# STM32F4xx_Schematic.net
KiCad netlist of a schematic drawn in Altium Designer
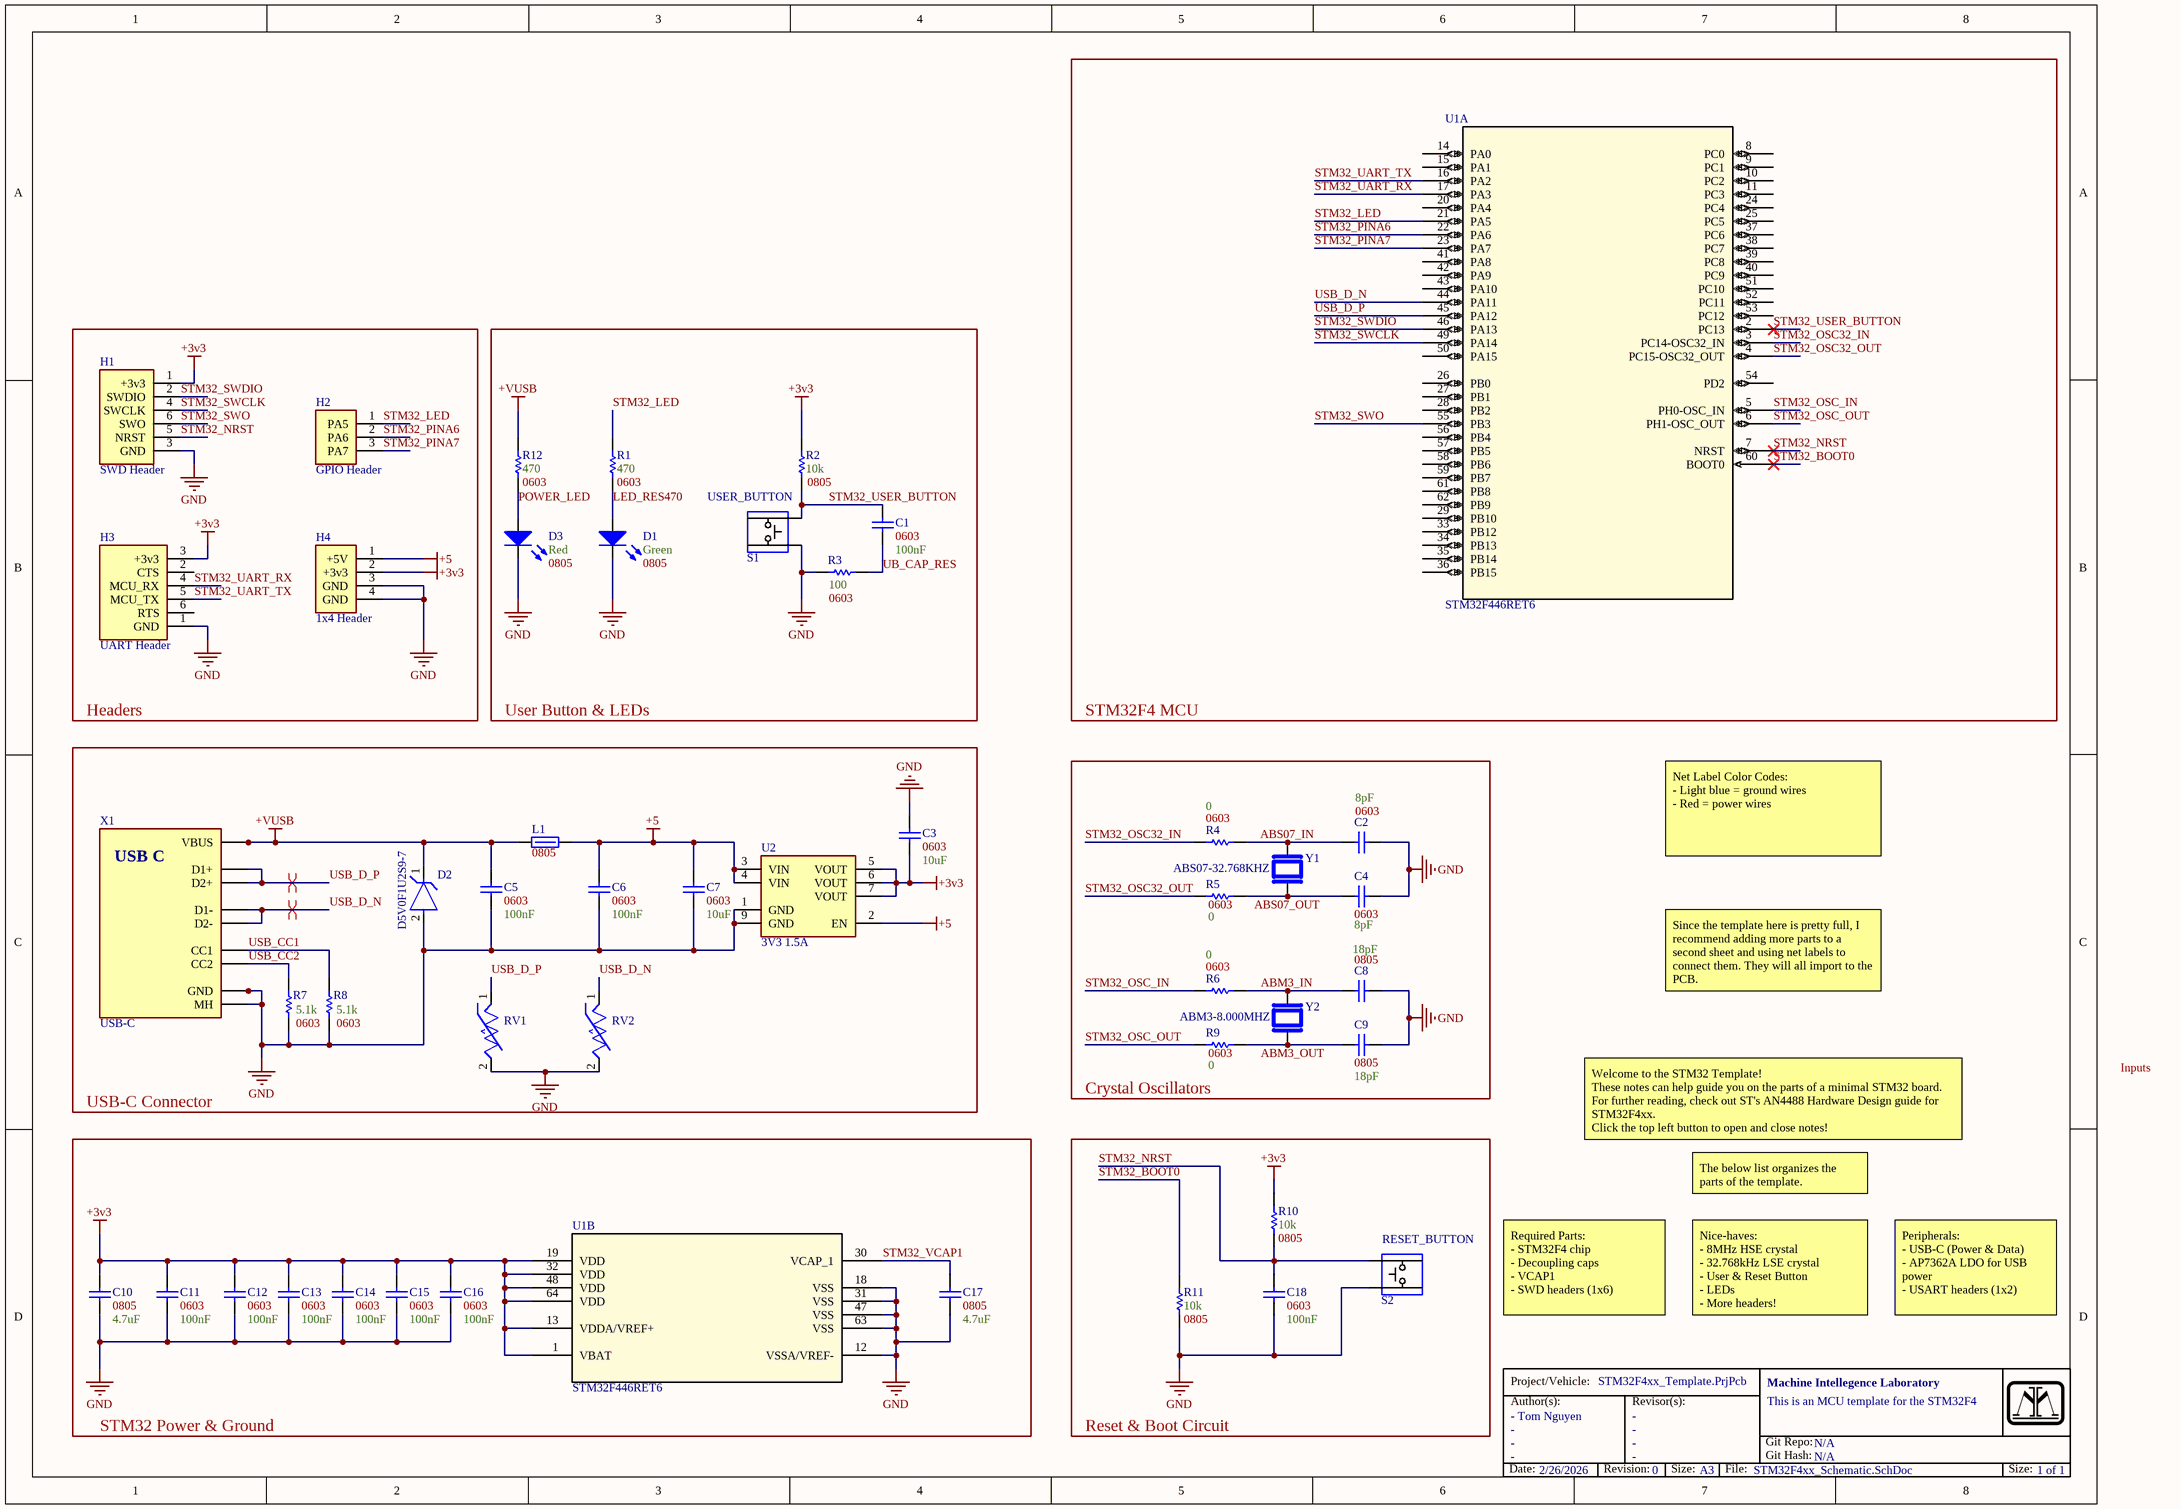
[diagram p0: STM32F4xx_Schematic.SchDoc]

(export (version "E")
  (design (tool "Eeschema 10.0.6"))
  (components
    (comp (ref "C1")
      (value "[Cap] 0603 0.1uF 10% 16V")
      (footprint "[Cap] SMD 0603")
      (description "CC0603KRX7R7BB104")
      (fields
        (field (name "SIZE PACKAGE") "0603")
        (field (name "TOLERANCE") "10%")
        (field (name "CAPACITANCE") "100nF")
      )
      (libsource (lib "Capacitors") (part "[Cap] 0603 0.1uF 10% 16V"))
    )
    (comp (ref "C2")
      (value "8pF")
      (footprint "[Cap] 0603 8pF ±0.1pF 50V")
      (description "GRM1555C1H8R0BA01D")
      (fields
        (field (name "SIZ") "0603")
        (field (name "CAPACITANCE") "8pF")
        (field (name "COPYRIGHT") "Copyright (C) 2026 Ultra Librarian. All rights reserved.")
      )
      (libsource (lib "STM32F4xx") (part "[Cap] 0603 8pF ±0.1pF 50V"))
    )
    (comp (ref "C3")
      (value "[Cap] 0603 10uF 10% 10V")
      (footprint "[Cap] SMD 0603")
      (description "CL10A106KP8NNNC")
      (fields
        (field (name "SIZE PACKAGE") "0603")
        (field (name "TOLERANCE") "10%")
        (field (name "CAPACITANCE") "10uF")
      )
      (libsource (lib "Capacitors") (part "[Cap] 0603 10uF 10% 10V"))
    )
    (comp (ref "C4")
      (value "8pF")
      (footprint "[Cap] 0603 8pF ±0.1pF 50V")
      (description "GRM1555C1H8R0BA01D")
      (fields
        (field (name "SIZ") "0603")
        (field (name "CAPACITANCE") "8pF")
        (field (name "COPYRIGHT") "Copyright (C) 2026 Ultra Librarian. All rights reserved.")
      )
      (libsource (lib "STM32F4xx") (part "[Cap] 0603 8pF ±0.1pF 50V"))
    )
    (comp (ref "C5")
      (value "[Cap] 0603 0.1uF 10% 16V")
      (footprint "[Cap] SMD 0603")
      (description "CC0603KRX7R7BB104")
      (fields
        (field (name "SIZE PACKAGE") "0603")
        (field (name "TOLERANCE") "10%")
        (field (name "CAPACITANCE") "100nF")
      )
      (libsource (lib "Capacitors") (part "[Cap] 0603 0.1uF 10% 16V"))
    )
    (comp (ref "C6")
      (value "[Cap] 0603 0.1uF 10% 16V")
      (footprint "[Cap] SMD 0603")
      (description "CC0603KRX7R7BB104")
      (fields
        (field (name "SIZE PACKAGE") "0603")
        (field (name "TOLERANCE") "10%")
        (field (name "CAPACITANCE") "100nF")
      )
      (libsource (lib "Capacitors") (part "[Cap] 0603 0.1uF 10% 16V"))
    )
    (comp (ref "C7")
      (value "[Cap] 0603 10uF 10% 10V")
      (footprint "[Cap] SMD 0603")
      (description "CL10A106KP8NNNC")
      (fields
        (field (name "SIZE PACKAGE") "0603")
        (field (name "TOLERANCE") "10%")
        (field (name "CAPACITANCE") "10uF")
      )
      (libsource (lib "Capacitors") (part "[Cap] 0603 10uF 10% 10V"))
    )
    (comp (ref "C8")
      (value "[Cap] 0805 18pF ±5% 250V")
      (footprint "[Cap] 0805 ±5% 250V")
      (description "GQM2195C2E180JB12D")
      (fields
        (field (name "MF") "Murata")
        (field (name "MP") "GQM2195C2E270JB12D")
        (field (name "SIZE") "0805")
        (field (name "CAPACITANCE") "18pF")
      )
      (libsource (lib "STM32F4xx") (part "[Cap] 0805 18pF ±5% 250V"))
    )
    (comp (ref "C9")
      (value "[Cap] 0805 18pF ±5% 250V")
      (footprint "[Cap] 0805 ±5% 250V")
      (description "GQM2195C2E180JB12D")
      (fields
        (field (name "MF") "Murata")
        (field (name "MP") "GQM2195C2E270JB12D")
        (field (name "SIZE") "0805")
        (field (name "CAPACITANCE") "18pF")
      )
      (libsource (lib "STM32F4xx") (part "[Cap] 0805 18pF ±5% 250V"))
    )
    (comp (ref "C10")
      (value "[Cap] 0805 4.7uF 10% 50V")
      (footprint "[Cap] SMD 0805")
      (description "GRT21BR61H475KE13L")
      (fields
        (field (name "SIZE PACKAGE") "0805")
        (field (name "TOLERANCE") "10%")
        (field (name "CAPACITANCE") "4.7uF")
      )
      (libsource (lib "Capacitors") (part "[Cap] 0805 4.7uF 10% 50V"))
    )
    (comp (ref "C11")
      (value "[Cap] 0603 0.1uF 10% 16V")
      (footprint "[Cap] SMD 0603")
      (description "CC0603KRX7R7BB104")
      (fields
        (field (name "SIZE PACKAGE") "0603")
        (field (name "TOLERANCE") "10%")
        (field (name "CAPACITANCE") "100nF")
      )
      (libsource (lib "Capacitors") (part "[Cap] 0603 0.1uF 10% 16V"))
    )
    (comp (ref "C12")
      (value "[Cap] 0603 0.1uF 10% 16V")
      (footprint "[Cap] SMD 0603")
      (description "CC0603KRX7R7BB104")
      (fields
        (field (name "SIZE PACKAGE") "0603")
        (field (name "TOLERANCE") "10%")
        (field (name "CAPACITANCE") "100nF")
      )
      (libsource (lib "Capacitors") (part "[Cap] 0603 0.1uF 10% 16V"))
    )
    (comp (ref "C13")
      (value "[Cap] 0603 0.1uF 10% 16V")
      (footprint "[Cap] SMD 0603")
      (description "CC0603KRX7R7BB104")
      (fields
        (field (name "SIZE PACKAGE") "0603")
        (field (name "TOLERANCE") "10%")
        (field (name "CAPACITANCE") "100nF")
      )
      (libsource (lib "Capacitors") (part "[Cap] 0603 0.1uF 10% 16V"))
    )
    (comp (ref "C14")
      (value "[Cap] 0603 0.1uF 10% 16V")
      (footprint "[Cap] SMD 0603")
      (description "CC0603KRX7R7BB104")
      (fields
        (field (name "SIZE PACKAGE") "0603")
        (field (name "TOLERANCE") "10%")
        (field (name "CAPACITANCE") "100nF")
      )
      (libsource (lib "Capacitors") (part "[Cap] 0603 0.1uF 10% 16V"))
    )
    (comp (ref "C15")
      (value "[Cap] 0603 0.1uF 10% 16V")
      (footprint "[Cap] SMD 0603")
      (description "CC0603KRX7R7BB104")
      (fields
        (field (name "SIZE PACKAGE") "0603")
        (field (name "TOLERANCE") "10%")
        (field (name "CAPACITANCE") "100nF")
      )
      (libsource (lib "Capacitors") (part "[Cap] 0603 0.1uF 10% 16V"))
    )
    (comp (ref "C16")
      (value "[Cap] 0603 0.1uF 10% 16V")
      (footprint "[Cap] SMD 0603")
      (description "CC0603KRX7R7BB104")
      (fields
        (field (name "SIZE PACKAGE") "0603")
        (field (name "TOLERANCE") "10%")
        (field (name "CAPACITANCE") "100nF")
      )
      (libsource (lib "Capacitors") (part "[Cap] 0603 0.1uF 10% 16V"))
    )
    (comp (ref "C17")
      (value "[Cap] 0805 4.7uF 10% 50V")
      (footprint "[Cap] SMD 0805")
      (description "GRT21BR61H475KE13L")
      (fields
        (field (name "SIZE PACKAGE") "0805")
        (field (name "TOLERANCE") "10%")
        (field (name "CAPACITANCE") "4.7uF")
      )
      (libsource (lib "Capacitors") (part "[Cap] 0805 4.7uF 10% 50V"))
    )
    (comp (ref "C18")
      (value "[Cap] 0603 0.1uF 10% 16V")
      (footprint "[Cap] SMD 0603")
      (description "CC0603KRX7R7BB104")
      (fields
        (field (name "SIZE PACKAGE") "0603")
        (field (name "TOLERANCE") "10%")
        (field (name "CAPACITANCE") "100nF")
      )
      (libsource (lib "Capacitors") (part "[Cap] 0603 0.1uF 10% 16V"))
    )
    (comp (ref "D1")
      (value "[LED] SMD 0805 Green")
      (footprint "[LED] SMD 0805")
      (description "LG R971-KN-1-0-20-R18")
      (fields (field (name "COLOR") "Green") (field (name "SIZE PACKAGE") "0805"))
      (libsource (lib "LEDs") (part "[LED] SMD 0805 Green"))
    )
    (comp (ref "D2")
      (value "Cathode side marked by line")
      (footprint "[TVS] Unidirectional for 5V ESD")
      (description "D5V0F1U2S9-7")
      (fields
        (field (name "SUPPLIER PART NUMBER 1") "D5V0F1U2S9-7")
        (field (name "COPYRIGHT") "Copyright (C) 2025 Ultra Librarian. All rights reserved.")
      )
      (libsource (lib "STM32F4xx") (part "[TVS] Unidirectional for 5V ESD"))
    )
    (comp (ref "D3")
      (value "[LED] SMD 0805 Red")
      (footprint "[LED] SMD 0805")
      (description "LS R976-NR-1-0-20-R18")
      (fields (field (name "COLOR") "Red") (field (name "SIZE PACKAGE") "0805"))
      (libsource (lib "LEDs") (part "[LED] SMD 0805 Red"))
    )
    (comp (ref "H1")
      (value "SWD Header")
      (footprint "[Header] 1x6 Male STM32 SWD")
      (description "2.54mm pitch")
      (libsource (lib "STM32F4xx") (part "[Header] 1x6 Male STM32 SWD"))
    )
    (comp (ref "H2")
      (value "GPIO Header")
      (footprint "[Header] 1x3 Male GPIO")
      (description "2.54mm pitch")
      (libsource (lib "STM32F4xx") (part "[Header] 1x3 Male GPIO"))
    )
    (comp (ref "H3")
      (value "UART Header")
      (footprint "[Header] 1x6 Male STM32 UART")
      (description "2.54mm pitch")
      (libsource (lib "STM32F4xx") (part "[Header] 1x6 Male STM32 UART"))
    )
    (comp (ref "H4")
      (value "1x4 Header")
      (footprint "[Header] 1x4 Male Power")
      (description "2.54mm pitch")
      (libsource (lib "STM32F4xx") (part "[Header] 1x4 Male Power"))
    )
    (comp (ref "L1")
      (value "652-MH2029-300Y")
      (footprint "[Ferrite] SMD 0805")
      (fields (field (name "SIZE PACKAGE") "0805"))
      (libsource (lib "Ferrite Beads") (part "[Ferrite] SMD 0805 3A 30ohm"))
    )
    (comp (ref "R1")
      (value "RC0603JR-13470RL")
      (footprint "RESC1608X55X25LL10T15")
      (fields
        (field (name "MANUFACTURER") "Yageo")
        (field (name "RESISTANCE") "470")
        (field (name "SIZE PACKAGE") "0603")
      )
      (libsource (lib "Altium Content Vault") (part "RES"))
    )
    (comp (ref "R2")
      (value "[10k] SMD 0603 1% 1/8W")
      (footprint "[Res] SMD 0603")
      (description "RC0805JR-0710KL")
      (fields
        (field (name "TOLERANCE") "5%")
        (field (name "RESISTANCE") "10k")
        (field (name "SIZE PACKAGE") "0805")
      )
      (libsource (lib "Resistors") (part "[10k] SMD 0603 1% 1/8W"))
    )
    (comp (ref "R3")
      (value "[100] SMD 0603 1% 1/10W")
      (footprint "[Res] SMD 0603")
      (description "RC0603FR-07100RL")
      (fields
        (field (name "TOLERANCE") "1%")
        (field (name "RESISTANCE") "100")
        (field (name "SIZE PACKAGE") "0603")
      )
      (libsource (lib "Resistors") (part "[100] SMD 0603 1% 1/10W"))
    )
    (comp (ref "R4")
      (value "[0] SMD 0603 5% 1/10W")
      (footprint "[0] SMD 0603 5% 1/10W")
      (description "RC0603JR-070RL")
      (fields
        (field (name "MF") "Yageo")
        (field (name "RESISTANCE") "0")
        (field (name "SIZE PACKAGE") "0603")
        (field (name "TOLERANCE") "5%")
      )
      (libsource (lib "STM32F4xx") (part "[0] SMD 0603 5% 1/10W"))
    )
    (comp (ref "R5")
      (value "[0] SMD 0603 5% 1/10W")
      (footprint "[0] SMD 0603 5% 1/10W")
      (description "RC0603JR-070RL")
      (fields
        (field (name "MF") "Yageo")
        (field (name "RESISTANCE") "0")
        (field (name "SIZE PACKAGE") "0603")
        (field (name "TOLERANCE") "5%")
      )
      (libsource (lib "STM32F4xx") (part "[0] SMD 0603 5% 1/10W"))
    )
    (comp (ref "R6")
      (value "[0] SMD 0603 5% 1/10W")
      (footprint "[0] SMD 0603 5% 1/10W")
      (description "RC0603JR-070RL")
      (fields
        (field (name "MF") "Yageo")
        (field (name "RESISTANCE") "0")
        (field (name "SIZE PACKAGE") "0603")
        (field (name "TOLERANCE") "5%")
      )
      (libsource (lib "STM32F4xx") (part "[0] SMD 0603 5% 1/10W"))
    )
    (comp (ref "R7")
      (value "[5.1k] SMD 0603 1% 1/10W")
      (footprint "[Res] SMD 0603")
      (description "RC0603FR-075K1L")
      (fields
        (field (name "TOLERANCE") "1%")
        (field (name "RESISTANCE") "5.1k")
        (field (name "SIZE PACKAGE") "0603")
      )
      (libsource (lib "Resistors") (part "[5.1k] SMD 0603 1% 1/10W"))
    )
    (comp (ref "R8")
      (value "[5.1k] SMD 0603 1% 1/10W")
      (footprint "[Res] SMD 0603")
      (description "RC0603FR-075K1L")
      (fields
        (field (name "TOLERANCE") "1%")
        (field (name "RESISTANCE") "5.1k")
        (field (name "SIZE PACKAGE") "0603")
      )
      (libsource (lib "Resistors") (part "[5.1k] SMD 0603 1% 1/10W"))
    )
    (comp (ref "R9")
      (value "[0] SMD 0603 5% 1/10W")
      (footprint "[0] SMD 0603 5% 1/10W")
      (description "RC0603JR-070RL")
      (fields
        (field (name "MF") "Yageo")
        (field (name "RESISTANCE") "0")
        (field (name "SIZE PACKAGE") "0603")
        (field (name "TOLERANCE") "5%")
      )
      (libsource (lib "STM32F4xx") (part "[0] SMD 0603 5% 1/10W"))
    )
    (comp (ref "R10")
      (value "[10k] SMD 0603 1% 1/8W")
      (footprint "[Res] SMD 0603")
      (description "RC0805JR-0710KL")
      (fields
        (field (name "TOLERANCE") "5%")
        (field (name "RESISTANCE") "10k")
        (field (name "SIZE PACKAGE") "0805")
      )
      (libsource (lib "Resistors") (part "[10k] SMD 0603 1% 1/8W"))
    )
    (comp (ref "R11")
      (value "[10k] SMD 0603 1% 1/8W")
      (footprint "[Res] SMD 0603")
      (description "RC0805JR-0710KL")
      (fields
        (field (name "TOLERANCE") "5%")
        (field (name "RESISTANCE") "10k")
        (field (name "SIZE PACKAGE") "0805")
      )
      (libsource (lib "Resistors") (part "[10k] SMD 0603 1% 1/8W"))
    )
    (comp (ref "R12")
      (value "RC0603JR-13470RL")
      (footprint "RESC1608X55X25LL10T15")
      (fields
        (field (name "MANUFACTURER") "Yageo")
        (field (name "RESISTANCE") "470")
        (field (name "SIZE PACKAGE") "0603")
      )
      (libsource (lib "Altium Content Vault") (part "RES"))
    )
    (comp (ref "RV1")
      (value "[ESD] SMD Varistor for USB 3.3V lines")
      (footprint "[ESD] SMD Varistor for USB 3.3V lines")
      (description "Varistor 1 Circuit Surface Mount, MLCV 0603 (1608 Metric) CG0603MLU-05E")
      (fields (field (name "MF") "Bourns") (field (name "MP") "CG0603MLU-05E"))
      (libsource (lib "STM32F4xx") (part "[ESD] SMD Varistor for USB 3.3V lines"))
    )
    (comp (ref "RV2")
      (value "[ESD] SMD Varistor for USB 3.3V lines")
      (footprint "[ESD] SMD Varistor for USB 3.3V lines")
      (description "Varistor 1 Circuit Surface Mount, MLCV 0603 (1608 Metric) CG0603MLU-05E")
      (fields (field (name "MF") "Bourns") (field (name "MP") "CG0603MLU-05E"))
      (libsource (lib "STM32F4xx") (part "[ESD] SMD Varistor for USB 3.3V lines"))
    )
    (comp (ref "S1")
      (value "Standard pushbutton")
      (footprint "[SPST] Pushbutton")
      (libsource (lib "Switches") (part "[SPST] Pushbutton"))
    )
    (comp (ref "S2")
      (value "Standard pushbutton")
      (footprint "[SPST] Pushbutton")
      (libsource (lib "") (part "[SPST] Pushbutton_1"))
    )
    (comp (ref "U1")
      (value "STM32F446RET6")
      (footprint "STM32F446RET6")
      (fields (field (name "COPYRIGHT") "Copyright (C) 2025 Ultra Librarian. All rights reserved."))
      (libsource (lib "STM32F4xx") (part "STM32F446RET6"))
    )
    (comp (ref "U2")
      (value "3V3 1.5A")
      (footprint "[Linear] 3V3 1.5A")
      (description "AP7362A-33SP-13")
      (libsource (lib "Voltage Regulators") (part "[Linear] 3V3 1.5A"))
    )
    (comp (ref "X1")
      (value "USB-C")
      (footprint "[USB] USB-C Right-Angle")
      (libsource (lib "STM32F4xx") (part "[USB] Type-C Right-Angle"))
    )
    (comp (ref "Y1")
      (value "ABS07-32.768KHZ")
      (footprint "ABS07-32.768KHZ")
      (description "ABS07-32.768KHZ-9-T, 32.768 kHz Â±20ppm Crystal 9pF 70 kOhms 2-SMD, No Lead")
      (fields (field (name "MF") "Abracon") (field (name "MP") "ABS07-32.768KHZ-9-T"))
      (libsource (lib "STM32F4xx") (part "ABS07-32.768KHZ"))
    )
    (comp (ref "Y2")
      (value "ABM3-8.000MHZ")
      (footprint "ABM3-8.000MHZ")
      (description "ABM3-8.000MHZ-D2Y-T, 8 MHz Â±20ppm Crystal 18pF 140 Ohms 2-SMD, No Lead")
      (fields (field (name "MP") "ABM3-8.000MHZ-D2Y-T") (field (name "MF") "Abracon"))
      (libsource (lib "STM32F4xx") (part "ABM3-8.000MHZ"))
    )
  )
  (nets
    (net (code "1") (name "+3v3") (class "Default")
      (node (ref "C10") (pin "2") (pinfunction "2_2") (pintype "passive"))
      (node (ref "C11") (pin "2") (pinfunction "2_2") (pintype "passive"))
      (node (ref "C12") (pin "1") (pinfunction "1_1") (pintype "passive"))
      (node (ref "C13") (pin "1") (pinfunction "1_1") (pintype "passive"))
      (node (ref "C14") (pin "1") (pinfunction "1_1") (pintype "passive"))
      (node (ref "C15") (pin "1") (pinfunction "1_1") (pintype "passive"))
      (node (ref "C16") (pin "2") (pinfunction "2_2") (pintype "passive"))
      (node (ref "C3") (pin "1") (pinfunction "1_1") (pintype "passive"))
      (node (ref "H1") (pin "1") (pinfunction "+3v3_1") (pintype "passive"))
      (node (ref "H3") (pin "3") (pinfunction "+3v3_3") (pintype "passive"))
      (node (ref "H4") (pin "2") (pinfunction "+3v3_2") (pintype "passive"))
      (node (ref "R10") (pin "2") (pinfunction "2_2") (pintype "passive"))
      (node (ref "R2") (pin "1") (pinfunction "1_1") (pintype "passive"))
      (node (ref "U1") (pin "1") (pinfunction "VBAT_1") (pintype "power_in"))
      (node (ref "U1") (pin "13") (pinfunction "VDDA/VREF+_13") (pintype "power_in"))
      (node (ref "U1") (pin "19") (pinfunction "VDD_19") (pintype "power_in"))
      (node (ref "U1") (pin "32") (pinfunction "VDD_32") (pintype "power_in"))
      (node (ref "U1") (pin "48") (pinfunction "VDD_48") (pintype "power_in"))
      (node (ref "U1") (pin "64") (pinfunction "VDD_64") (pintype "power_in"))
      (node (ref "U2") (pin "5") (pinfunction "VOUT_5") (pintype "passive"))
      (node (ref "U2") (pin "6") (pinfunction "VOUT_6") (pintype "passive"))
      (node (ref "U2") (pin "7") (pinfunction "VOUT_7") (pintype "passive"))
    )
    (net (code "2") (name "+5") (class "Default")
      (node (ref "C6") (pin "1") (pinfunction "1_1") (pintype "passive"))
      (node (ref "C7") (pin "2") (pinfunction "2_2") (pintype "passive"))
      (node (ref "H4") (pin "1") (pinfunction "+5V_1") (pintype "passive"))
      (node (ref "L1") (pin "2") (pinfunction "2_2") (pintype "passive"))
      (node (ref "U2") (pin "2") (pinfunction "EN_2") (pintype "passive"))
      (node (ref "U2") (pin "3") (pinfunction "VIN_3") (pintype "passive"))
      (node (ref "U2") (pin "4") (pinfunction "VIN_4") (pintype "passive"))
    )
    (net (code "3") (name "+VUSB") (class "Default")
      (node (ref "C5") (pin "1") (pinfunction "1_1") (pintype "passive"))
      (node (ref "D2") (pin "1") (pinfunction "1_1") (pintype "passive"))
      (node (ref "L1") (pin "1") (pinfunction "1_1") (pintype "passive"))
      (node (ref "R12") (pin "1") (pinfunction "1_1") (pintype "passive"))
      (node (ref "X1") (pin "A4") (pinfunction "VBUS_A4") (pintype "passive"))
      (node (ref "X1") (pin "A9") (pinfunction "VBUS_A9") (pintype "passive"))
      (node (ref "X1") (pin "B4") (pinfunction "VBUS_B4") (pintype "passive"))
      (node (ref "X1") (pin "B9") (pinfunction "VBUS_B9") (pintype "passive"))
    )
    (net (code "4") (name "/ABM3_IN") (class "Default")
      (node (ref "C8") (pin "1") (pinfunction "1_1") (pintype "passive"))
      (node (ref "R6") (pin "2") (pinfunction "2_2") (pintype "passive"))
      (node (ref "Y2") (pin "2") (pinfunction "2_2") (pintype "passive"))
    )
    (net (code "5") (name "/ABM3_OUT") (class "Default")
      (node (ref "C9") (pin "1") (pinfunction "1_1") (pintype "passive"))
      (node (ref "R9") (pin "2") (pinfunction "2_2") (pintype "passive"))
      (node (ref "Y2") (pin "1") (pinfunction "1_1") (pintype "passive"))
    )
    (net (code "6") (name "/ABS07_IN") (class "Default")
      (node (ref "C2") (pin "1") (pinfunction "1_1") (pintype "passive"))
      (node (ref "R4") (pin "2") (pinfunction "2_2") (pintype "passive"))
      (node (ref "Y1") (pin "1") (pinfunction "1_1") (pintype "passive"))
    )
    (net (code "7") (name "/ABS07_OUT") (class "Default")
      (node (ref "C4") (pin "1") (pinfunction "1_1") (pintype "passive"))
      (node (ref "R5") (pin "2") (pinfunction "2_2") (pintype "passive"))
      (node (ref "Y1") (pin "2") (pinfunction "2_2") (pintype "passive"))
    )
    (net (code "8") (name "/LED_RES470") (class "Default")
      (node (ref "D1") (pin "1") (pinfunction "Anode_1") (pintype "passive"))
      (node (ref "R1") (pin "2") (pinfunction "2_2") (pintype "passive"))
    )
    (net (code "9") (name "/POWER_LED") (class "Default")
      (node (ref "D3") (pin "1") (pinfunction "Anode_1") (pintype "passive"))
      (node (ref "R12") (pin "2") (pinfunction "2_2") (pintype "passive"))
    )
    (net (code "10") (name "/STM32_BOOT0") (class "Default")
      (node (ref "R11") (pin "1") (pinfunction "1_1") (pintype "passive"))
      (node (ref "U1") (pin "60") (pinfunction "BOOT0_60") (pintype "input"))
    )
    (net (code "11") (name "/STM32_LED") (class "Default")
      (node (ref "H2") (pin "1") (pinfunction "PA5_1") (pintype "passive"))
      (node (ref "R1") (pin "1") (pinfunction "1_1") (pintype "passive"))
      (node (ref "U1") (pin "21") (pinfunction "PA5_21") (pintype "bidirectional"))
    )
    (net (code "12") (name "/STM32_NRST") (class "Default")
      (node (ref "C18") (pin "1") (pinfunction "1_1") (pintype "passive"))
      (node (ref "H1") (pin "5") (pinfunction "NRST_5") (pintype "passive"))
      (node (ref "R10") (pin "1") (pinfunction "1_1") (pintype "passive"))
      (node (ref "S2") (pin "1") (pintype "power_in"))
      (node (ref "U1") (pin "7") (pinfunction "NRST_7") (pintype "bidirectional"))
    )
    (net (code "13") (name "/STM32_OSC32_IN") (class "Default")
      (node (ref "R4") (pin "1") (pinfunction "1_1") (pintype "passive"))
      (node (ref "U1") (pin "3") (pinfunction "PC14-OSC32_IN_3") (pintype "bidirectional"))
    )
    (net (code "14") (name "/STM32_OSC32_OUT") (class "Default")
      (node (ref "R5") (pin "1") (pinfunction "1_1") (pintype "passive"))
      (node (ref "U1") (pin "4") (pinfunction "PC15-OSC32_OUT_4") (pintype "bidirectional"))
    )
    (net (code "15") (name "/STM32_OSC_IN") (class "Default")
      (node (ref "R6") (pin "1") (pinfunction "1_1") (pintype "passive"))
      (node (ref "U1") (pin "5") (pinfunction "PH0-OSC_IN_5") (pintype "bidirectional"))
    )
    (net (code "16") (name "/STM32_OSC_OUT") (class "Default")
      (node (ref "R9") (pin "1") (pinfunction "1_1") (pintype "passive"))
      (node (ref "U1") (pin "6") (pinfunction "PH1-OSC_OUT_6") (pintype "bidirectional"))
    )
    (net (code "17") (name "/STM32_PINA6") (class "Default")
      (node (ref "H2") (pin "2") (pinfunction "PA6_2") (pintype "passive"))
      (node (ref "U1") (pin "22") (pinfunction "PA6_22") (pintype "bidirectional"))
    )
    (net (code "18") (name "/STM32_PINA7") (class "Default")
      (node (ref "H2") (pin "3") (pinfunction "PA7_3") (pintype "passive"))
      (node (ref "U1") (pin "23") (pinfunction "PA7_23") (pintype "bidirectional"))
    )
    (net (code "19") (name "/STM32_SWCLK") (class "Default")
      (node (ref "H1") (pin "4") (pinfunction "SWCLK_4") (pintype "passive"))
      (node (ref "U1") (pin "49") (pinfunction "PA14_49") (pintype "bidirectional"))
    )
    (net (code "20") (name "/STM32_SWDIO") (class "Default")
      (node (ref "H1") (pin "2") (pinfunction "SWDIO_2") (pintype "passive"))
      (node (ref "U1") (pin "46") (pinfunction "PA13_46") (pintype "bidirectional"))
    )
    (net (code "21") (name "/STM32_SWO") (class "Default")
      (node (ref "H1") (pin "6") (pinfunction "SWO_6") (pintype "passive"))
      (node (ref "U1") (pin "55") (pinfunction "PB3_55") (pintype "bidirectional"))
    )
    (net (code "22") (name "/STM32_UART_RX") (class "Default")
      (node (ref "H3") (pin "4") (pinfunction "MCU_RX_4") (pintype "passive"))
      (node (ref "U1") (pin "17") (pinfunction "PA3_17") (pintype "bidirectional"))
    )
    (net (code "23") (name "/STM32_UART_TX") (class "Default")
      (node (ref "H3") (pin "5") (pinfunction "MCU_TX_5") (pintype "passive"))
      (node (ref "U1") (pin "16") (pinfunction "PA2_16") (pintype "bidirectional"))
    )
    (net (code "24") (name "/STM32_USER_BUTTON") (class "Default")
      (node (ref "C1") (pin "2") (pinfunction "2_2") (pintype "passive"))
      (node (ref "R2") (pin "2") (pinfunction "2_2") (pintype "passive"))
      (node (ref "S1") (pin "2") (pintype "power_in"))
      (node (ref "U1") (pin "2") (pinfunction "PC13_2") (pintype "bidirectional"))
    )
    (net (code "25") (name "/STM32_VCAP1") (class "Default")
      (node (ref "C17") (pin "2") (pinfunction "2_2") (pintype "passive"))
      (node (ref "U1") (pin "30") (pinfunction "VCAP_1_30") (pintype "power_in"))
    )
    (net (code "26") (name "/UB_CAP_RES") (class "Default")
      (node (ref "C1") (pin "1") (pinfunction "1_1") (pintype "passive"))
      (node (ref "R3") (pin "2") (pinfunction "2_2") (pintype "passive"))
    )
    (net (code "27") (name "/USB_CC1") (class "Default")
      (node (ref "R8") (pin "1") (pinfunction "1_1") (pintype "passive"))
      (node (ref "X1") (pin "A5") (pinfunction "CC1_A5") (pintype "passive"))
    )
    (net (code "28") (name "/USB_CC2") (class "Default")
      (node (ref "R7") (pin "1") (pinfunction "1_1") (pintype "passive"))
      (node (ref "X1") (pin "B5") (pinfunction "CC2_B5") (pintype "passive"))
    )
    (net (code "29") (name "/USB_D_N") (class "Default")
      (node (ref "RV2") (pin "1") (pinfunction "1_1") (pintype "passive"))
      (node (ref "U1") (pin "44") (pinfunction "PA11_44") (pintype "bidirectional"))
      (node (ref "X1") (pin "A7") (pinfunction "D1-_A7") (pintype "passive"))
      (node (ref "X1") (pin "B7") (pinfunction "D2-_B7") (pintype "passive"))
    )
    (net (code "30") (name "/USB_D_P") (class "Default")
      (node (ref "RV1") (pin "1") (pinfunction "1_1") (pintype "passive"))
      (node (ref "U1") (pin "45") (pinfunction "PA12_45") (pintype "bidirectional"))
      (node (ref "X1") (pin "A6") (pinfunction "D1+_A6") (pintype "passive"))
      (node (ref "X1") (pin "B6") (pinfunction "D2+_B6") (pintype "passive"))
    )
    (net (code "31") (name "GND") (class "Default")
      (node (ref "C10") (pin "1") (pinfunction "1_1") (pintype "passive"))
      (node (ref "C11") (pin "1") (pinfunction "1_1") (pintype "passive"))
      (node (ref "C12") (pin "2") (pinfunction "2_2") (pintype "passive"))
      (node (ref "C13") (pin "2") (pinfunction "2_2") (pintype "passive"))
      (node (ref "C14") (pin "2") (pinfunction "2_2") (pintype "passive"))
      (node (ref "C15") (pin "2") (pinfunction "2_2") (pintype "passive"))
      (node (ref "C16") (pin "1") (pinfunction "1_1") (pintype "passive"))
      (node (ref "C17") (pin "1") (pinfunction "1_1") (pintype "passive"))
      (node (ref "C18") (pin "2") (pinfunction "2_2") (pintype "passive"))
      (node (ref "C2") (pin "2") (pinfunction "2_2") (pintype "passive"))
      (node (ref "C3") (pin "2") (pinfunction "2_2") (pintype "passive"))
      (node (ref "C4") (pin "2") (pinfunction "2_2") (pintype "passive"))
      (node (ref "C5") (pin "2") (pinfunction "2_2") (pintype "passive"))
      (node (ref "C6") (pin "2") (pinfunction "2_2") (pintype "passive"))
      (node (ref "C7") (pin "1") (pinfunction "1_1") (pintype "passive"))
      (node (ref "C8") (pin "2") (pinfunction "2_2") (pintype "passive"))
      (node (ref "C9") (pin "2") (pinfunction "2_2") (pintype "passive"))
      (node (ref "D1") (pin "2") (pinfunction "Cathode_2") (pintype "passive"))
      (node (ref "D2") (pin "2") (pinfunction "2_2") (pintype "passive"))
      (node (ref "D3") (pin "2") (pinfunction "Cathode_2") (pintype "passive"))
      (node (ref "H1") (pin "3") (pinfunction "GND_3") (pintype "passive"))
      (node (ref "H3") (pin "1") (pinfunction "GND_1") (pintype "passive"))
      (node (ref "H4") (pin "3") (pinfunction "GND_3") (pintype "passive"))
      (node (ref "H4") (pin "4") (pinfunction "GND_4") (pintype "passive"))
      (node (ref "R11") (pin "2") (pinfunction "2_2") (pintype "passive"))
      (node (ref "R3") (pin "1") (pinfunction "1_1") (pintype "passive"))
      (node (ref "R7") (pin "2") (pinfunction "2_2") (pintype "passive"))
      (node (ref "R8") (pin "2") (pinfunction "2_2") (pintype "passive"))
      (node (ref "RV1") (pin "2") (pinfunction "2_2") (pintype "passive"))
      (node (ref "RV2") (pin "2") (pinfunction "2_2") (pintype "passive"))
      (node (ref "S1") (pin "1") (pintype "power_in"))
      (node (ref "S2") (pin "2") (pintype "power_in"))
      (node (ref "U1") (pin "12") (pinfunction "VSSA/VREF-_12") (pintype "power_in"))
      (node (ref "U1") (pin "18") (pinfunction "VSS_18") (pintype "power_in"))
      (node (ref "U1") (pin "31") (pinfunction "VSS_31") (pintype "power_in"))
      (node (ref "U1") (pin "47") (pinfunction "VSS_47") (pintype "power_in"))
      (node (ref "U1") (pin "63") (pinfunction "VSS_63") (pintype "power_in"))
      (node (ref "U2") (pin "1") (pinfunction "GND_1") (pintype "passive"))
      (node (ref "U2") (pin "9") (pinfunction "GND_9") (pintype "passive"))
      (node (ref "X1") (pin "A1") (pinfunction "GND_A1") (pintype "passive"))
      (node (ref "X1") (pin "A12") (pinfunction "GND_A12") (pintype "passive"))
      (node (ref "X1") (pin "B1") (pinfunction "GND_B1") (pintype "passive"))
      (node (ref "X1") (pin "B12") (pinfunction "GND_B12") (pintype "passive"))
      (node (ref "X1") (pin "MH") (pinfunction "MH_MH") (pintype "passive"))
    )
    (net (code "32") (name "unconnected-(H3-CTS-Pad2)") (class "Default")
      (node (ref "H3") (pin "2") (pinfunction "CTS_2") (pintype "passive"))
    )
    (net (code "33") (name "unconnected-(H3-RTS-Pad6)") (class "Default")
      (node (ref "H3") (pin "6") (pinfunction "RTS_6") (pintype "passive"))
    )
    (net (code "34") (name "unconnected-(U1A-PA0-Pad14)") (class "Default")
      (node (ref "U1") (pin "14") (pinfunction "PA0_14") (pintype "bidirectional"))
    )
    (net (code "35") (name "unconnected-(U1A-PA1-Pad15)") (class "Default")
      (node (ref "U1") (pin "15") (pinfunction "PA1_15") (pintype "bidirectional"))
    )
    (net (code "36") (name "unconnected-(U1A-PA4-Pad20)") (class "Default")
      (node (ref "U1") (pin "20") (pinfunction "PA4_20") (pintype "bidirectional"))
    )
    (net (code "37") (name "unconnected-(U1A-PA8-Pad41)") (class "Default")
      (node (ref "U1") (pin "41") (pinfunction "PA8_41") (pintype "bidirectional"))
    )
    (net (code "38") (name "unconnected-(U1A-PA9-Pad42)") (class "Default")
      (node (ref "U1") (pin "42") (pinfunction "PA9_42") (pintype "bidirectional"))
    )
    (net (code "39") (name "unconnected-(U1A-PA10-Pad43)") (class "Default")
      (node (ref "U1") (pin "43") (pinfunction "PA10_43") (pintype "bidirectional"))
    )
    (net (code "40") (name "unconnected-(U1A-PA15-Pad50)") (class "Default")
      (node (ref "U1") (pin "50") (pinfunction "PA15_50") (pintype "bidirectional"))
    )
    (net (code "41") (name "unconnected-(U1A-PB0-Pad26)") (class "Default")
      (node (ref "U1") (pin "26") (pinfunction "PB0_26") (pintype "bidirectional"))
    )
    (net (code "42") (name "unconnected-(U1A-PB1-Pad27)") (class "Default")
      (node (ref "U1") (pin "27") (pinfunction "PB1_27") (pintype "bidirectional"))
    )
    (net (code "43") (name "unconnected-(U1A-PB2-Pad28)") (class "Default")
      (node (ref "U1") (pin "28") (pinfunction "PB2_28") (pintype "bidirectional"))
    )
    (net (code "44") (name "unconnected-(U1A-PB4-Pad56)") (class "Default")
      (node (ref "U1") (pin "56") (pinfunction "PB4_56") (pintype "bidirectional"))
    )
    (net (code "45") (name "unconnected-(U1A-PB5-Pad57)") (class "Default")
      (node (ref "U1") (pin "57") (pinfunction "PB5_57") (pintype "bidirectional"))
    )
    (net (code "46") (name "unconnected-(U1A-PB6-Pad58)") (class "Default")
      (node (ref "U1") (pin "58") (pinfunction "PB6_58") (pintype "bidirectional"))
    )
    (net (code "47") (name "unconnected-(U1A-PB7-Pad59)") (class "Default")
      (node (ref "U1") (pin "59") (pinfunction "PB7_59") (pintype "bidirectional"))
    )
    (net (code "48") (name "unconnected-(U1A-PB8-Pad61)") (class "Default")
      (node (ref "U1") (pin "61") (pinfunction "PB8_61") (pintype "bidirectional"))
    )
    (net (code "49") (name "unconnected-(U1A-PB9-Pad62)") (class "Default")
      (node (ref "U1") (pin "62") (pinfunction "PB9_62") (pintype "bidirectional"))
    )
    (net (code "50") (name "unconnected-(U1A-PB10-Pad29)") (class "Default")
      (node (ref "U1") (pin "29") (pinfunction "PB10_29") (pintype "bidirectional"))
    )
    (net (code "51") (name "unconnected-(U1A-PB12-Pad33)") (class "Default")
      (node (ref "U1") (pin "33") (pinfunction "PB12_33") (pintype "bidirectional"))
    )
    (net (code "52") (name "unconnected-(U1A-PB13-Pad34)") (class "Default")
      (node (ref "U1") (pin "34") (pinfunction "PB13_34") (pintype "bidirectional"))
    )
    (net (code "53") (name "unconnected-(U1A-PB14-Pad35)") (class "Default")
      (node (ref "U1") (pin "35") (pinfunction "PB14_35") (pintype "bidirectional"))
    )
    (net (code "54") (name "unconnected-(U1A-PB15-Pad36)") (class "Default")
      (node (ref "U1") (pin "36") (pinfunction "PB15_36") (pintype "bidirectional"))
    )
    (net (code "55") (name "unconnected-(U1A-PC0-Pad8)") (class "Default")
      (node (ref "U1") (pin "8") (pinfunction "PC0_8") (pintype "bidirectional"))
    )
    (net (code "56") (name "unconnected-(U1A-PC1-Pad9)") (class "Default")
      (node (ref "U1") (pin "9") (pinfunction "PC1_9") (pintype "bidirectional"))
    )
    (net (code "57") (name "unconnected-(U1A-PC2-Pad10)") (class "Default")
      (node (ref "U1") (pin "10") (pinfunction "PC2_10") (pintype "bidirectional"))
    )
    (net (code "58") (name "unconnected-(U1A-PC3-Pad11)") (class "Default")
      (node (ref "U1") (pin "11") (pinfunction "PC3_11") (pintype "bidirectional"))
    )
    (net (code "59") (name "unconnected-(U1A-PC4-Pad24)") (class "Default")
      (node (ref "U1") (pin "24") (pinfunction "PC4_24") (pintype "bidirectional"))
    )
    (net (code "60") (name "unconnected-(U1A-PC5-Pad25)") (class "Default")
      (node (ref "U1") (pin "25") (pinfunction "PC5_25") (pintype "bidirectional"))
    )
    (net (code "61") (name "unconnected-(U1A-PC6-Pad37)") (class "Default")
      (node (ref "U1") (pin "37") (pinfunction "PC6_37") (pintype "bidirectional"))
    )
    (net (code "62") (name "unconnected-(U1A-PC7-Pad38)") (class "Default")
      (node (ref "U1") (pin "38") (pinfunction "PC7_38") (pintype "bidirectional"))
    )
    (net (code "63") (name "unconnected-(U1A-PC8-Pad39)") (class "Default")
      (node (ref "U1") (pin "39") (pinfunction "PC8_39") (pintype "bidirectional"))
    )
    (net (code "64") (name "unconnected-(U1A-PC9-Pad40)") (class "Default")
      (node (ref "U1") (pin "40") (pinfunction "PC9_40") (pintype "bidirectional"))
    )
    (net (code "65") (name "unconnected-(U1A-PC10-Pad51)") (class "Default")
      (node (ref "U1") (pin "51") (pinfunction "PC10_51") (pintype "bidirectional"))
    )
    (net (code "66") (name "unconnected-(U1A-PC11-Pad52)") (class "Default")
      (node (ref "U1") (pin "52") (pinfunction "PC11_52") (pintype "bidirectional"))
    )
    (net (code "67") (name "unconnected-(U1A-PC12-Pad53)") (class "Default")
      (node (ref "U1") (pin "53") (pinfunction "PC12_53") (pintype "bidirectional"))
    )
    (net (code "68") (name "unconnected-(U1A-PD2-Pad54)") (class "Default")
      (node (ref "U1") (pin "54") (pinfunction "PD2_54") (pintype "bidirectional"))
    )
  )
)
